# Display.net
KiCad netlist of a schematic drawn in Altium Designer
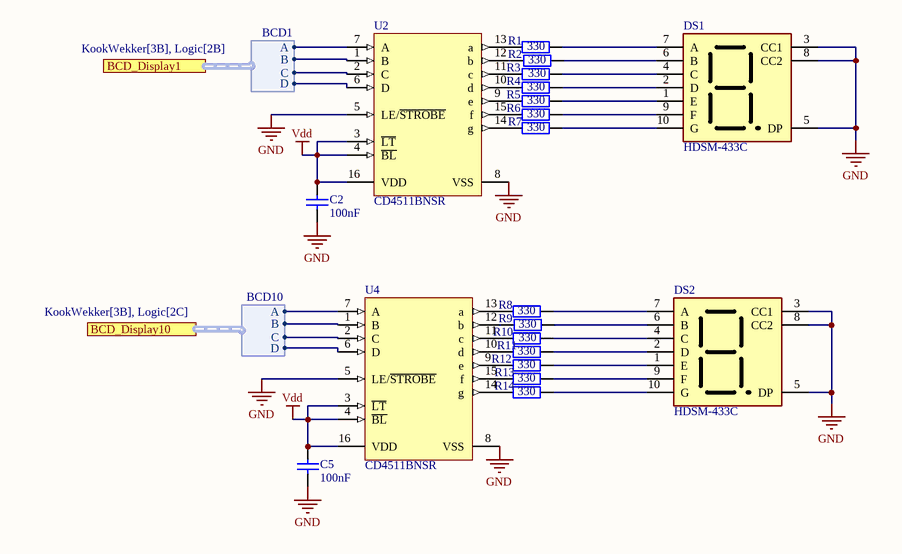
[diagram p0: Display.SchDoc]

(export (version "E")
  (design (tool "Eeschema 10.0.6"))
  (components
    (comp (ref "C2")
      (value "100nF")
      (footprint "C1206")
      (description "SMD Capacitor 1206")
      (fields (field (name "PUBLISHER") "Windesheim"))
      (libsource (lib "KookwekkerLibrary_v5_1") (part "Capacitor_1206"))
    )
    (comp (ref "C5")
      (value "100nF")
      (footprint "C1206")
      (description "SMD Capacitor 1206")
      (fields (field (name "PUBLISHER") "Windesheim"))
      (libsource (lib "KookwekkerLibrary_v5_1") (part "Capacitor_1206"))
    )
    (comp (ref "DS1")
      (value "HDSM-433C")
      (footprint "HDSM433C")
      (description "Display")
      (fields (field (name "MOUSER PART NUMBER") "630-HDSM-433C") (field (name "RS PART NUMBER") "1783057"))
      (libsource (lib "KookwekkerLibrary_v5_1") (part "HDSM-433C"))
    )
    (comp (ref "DS2")
      (value "HDSM-433C")
      (footprint "HDSM433C")
      (description "Display")
      (fields (field (name "MOUSER PART NUMBER") "630-HDSM-433C") (field (name "RS PART NUMBER") "1783057"))
      (libsource (lib "KookwekkerLibrary_v5_1") (part "HDSM-433C"))
    )
    (comp (ref "R1")
      (value "330")
      (footprint "R1206")
      (description "SMD Resistor 1206")
      (fields (field (name "PUBLISHER") "Windesheim"))
      (libsource (lib "KookwekkerLibrary_v5_1") (part "Resistor_1206"))
    )
    (comp (ref "R2")
      (value "330")
      (footprint "R1206")
      (description "SMD Resistor 1206")
      (fields (field (name "PUBLISHER") "Windesheim"))
      (libsource (lib "KookwekkerLibrary_v5_1") (part "Resistor_1206"))
    )
    (comp (ref "R3")
      (value "330")
      (footprint "R1206")
      (description "SMD Resistor 1206")
      (fields (field (name "PUBLISHER") "Windesheim"))
      (libsource (lib "KookwekkerLibrary_v5_1") (part "Resistor_1206"))
    )
    (comp (ref "R4")
      (value "330")
      (footprint "R1206")
      (description "SMD Resistor 1206")
      (fields (field (name "PUBLISHER") "Windesheim"))
      (libsource (lib "KookwekkerLibrary_v5_1") (part "Resistor_1206"))
    )
    (comp (ref "R5")
      (value "330")
      (footprint "R1206")
      (description "SMD Resistor 1206")
      (fields (field (name "PUBLISHER") "Windesheim"))
      (libsource (lib "KookwekkerLibrary_v5_1") (part "Resistor_1206"))
    )
    (comp (ref "R6")
      (value "330")
      (footprint "R1206")
      (description "SMD Resistor 1206")
      (fields (field (name "PUBLISHER") "Windesheim"))
      (libsource (lib "KookwekkerLibrary_v5_1") (part "Resistor_1206"))
    )
    (comp (ref "R7")
      (value "330")
      (footprint "R1206")
      (description "SMD Resistor 1206")
      (fields (field (name "PUBLISHER") "Windesheim"))
      (libsource (lib "KookwekkerLibrary_v5_1") (part "Resistor_1206"))
    )
    (comp (ref "R8")
      (value "330")
      (footprint "R1206")
      (description "SMD Resistor 1206")
      (fields (field (name "PUBLISHER") "Windesheim"))
      (libsource (lib "KookwekkerLibrary_v5_1") (part "Resistor_1206"))
    )
    (comp (ref "R9")
      (value "330")
      (footprint "R1206")
      (description "SMD Resistor 1206")
      (fields (field (name "PUBLISHER") "Windesheim"))
      (libsource (lib "KookwekkerLibrary_v5_1") (part "Resistor_1206"))
    )
    (comp (ref "R10")
      (value "330")
      (footprint "R1206")
      (description "SMD Resistor 1206")
      (fields (field (name "PUBLISHER") "Windesheim"))
      (libsource (lib "KookwekkerLibrary_v5_1") (part "Resistor_1206"))
    )
    (comp (ref "R11")
      (value "330")
      (footprint "R1206")
      (description "SMD Resistor 1206")
      (fields (field (name "PUBLISHER") "Windesheim"))
      (libsource (lib "KookwekkerLibrary_v5_1") (part "Resistor_1206"))
    )
    (comp (ref "R12")
      (value "330")
      (footprint "R1206")
      (description "SMD Resistor 1206")
      (fields (field (name "PUBLISHER") "Windesheim"))
      (libsource (lib "KookwekkerLibrary_v5_1") (part "Resistor_1206"))
    )
    (comp (ref "R13")
      (value "330")
      (footprint "R1206")
      (description "SMD Resistor 1206")
      (fields (field (name "PUBLISHER") "Windesheim"))
      (libsource (lib "KookwekkerLibrary_v5_1") (part "Resistor_1206"))
    )
    (comp (ref "R14")
      (value "330")
      (footprint "R1206")
      (description "SMD Resistor 1206")
      (fields (field (name "PUBLISHER") "Windesheim"))
      (libsource (lib "KookwekkerLibrary_v5_1") (part "Resistor_1206"))
    )
    (comp (ref "U2")
      (value "CD4511BNSR")
      (footprint "TI-NS16_N")
      (fields (field (name "MANUFACTURER") "Texas Instruments"))
      (libsource (lib "KookwekkerLibrary_v5_1") (part "CD4511BNSR"))
    )
    (comp (ref "U4")
      (value "CD4511BNSR")
      (footprint "TI-NS16_N")
      (fields (field (name "MANUFACTURER") "Texas Instruments"))
      (libsource (lib "KookwekkerLibrary_v5_1") (part "CD4511BNSR"))
    )
  )
  (nets
    (net (code "5") (name "GND") (class "Default")
      (node (ref "C2") (pin "1") (pinfunction "1_1") (pintype "passive"))
      (node (ref "C5") (pin "1") (pinfunction "1_1") (pintype "passive"))
      (node (ref "DS1") (pin "3") (pinfunction "CC1_3") (pintype "passive"))
      (node (ref "DS1") (pin "5") (pinfunction "DP_5") (pintype "passive"))
      (node (ref "DS1") (pin "8") (pinfunction "CC2_8") (pintype "passive"))
      (node (ref "DS2") (pin "3") (pinfunction "CC1_3") (pintype "passive"))
      (node (ref "DS2") (pin "5") (pinfunction "DP_5") (pintype "passive"))
      (node (ref "DS2") (pin "8") (pinfunction "CC2_8") (pintype "passive"))
      (node (ref "U2") (pin "5") (pinfunction "LE/~{STROBE}_5") (pintype "input"))
      (node (ref "U2") (pin "8") (pinfunction "VSS_8") (pintype "power_in"))
      (node (ref "U4") (pin "5") (pinfunction "LE/~{STROBE}_5") (pintype "input"))
      (node (ref "U4") (pin "8") (pinfunction "VSS_8") (pintype "power_in"))
    )
    (net (code "6") (name "Net-(DS1-A)") (class "Default")
      (node (ref "DS1") (pin "7") (pinfunction "A_7") (pintype "passive"))
      (node (ref "R1") (pin "2") (pinfunction "2_2") (pintype "passive"))
    )
    (net (code "7") (name "Net-(DS1-B)") (class "Default")
      (node (ref "DS1") (pin "6") (pinfunction "B_6") (pintype "passive"))
      (node (ref "R2") (pin "2") (pinfunction "2_2") (pintype "passive"))
    )
    (net (code "8") (name "Net-(DS1-C)") (class "Default")
      (node (ref "DS1") (pin "4") (pinfunction "C_4") (pintype "passive"))
      (node (ref "R3") (pin "2") (pinfunction "2_2") (pintype "passive"))
    )
    (net (code "9") (name "Net-(DS1-D)") (class "Default")
      (node (ref "DS1") (pin "2") (pinfunction "D_2") (pintype "passive"))
      (node (ref "R4") (pin "2") (pinfunction "2_2") (pintype "passive"))
    )
    (net (code "10") (name "Net-(DS1-E)") (class "Default")
      (node (ref "DS1") (pin "1") (pinfunction "E_1") (pintype "passive"))
      (node (ref "R5") (pin "2") (pinfunction "2_2") (pintype "passive"))
    )
    (net (code "11") (name "Net-(DS1-F)") (class "Default")
      (node (ref "DS1") (pin "9") (pinfunction "F_9") (pintype "passive"))
      (node (ref "R6") (pin "2") (pinfunction "2_2") (pintype "passive"))
    )
    (net (code "12") (name "Net-(DS1-G)") (class "Default")
      (node (ref "DS1") (pin "10") (pinfunction "G_10") (pintype "passive"))
      (node (ref "R7") (pin "2") (pinfunction "2_2") (pintype "passive"))
    )
    (net (code "13") (name "Net-(DS2-A)") (class "Default")
      (node (ref "DS2") (pin "7") (pinfunction "A_7") (pintype "passive"))
      (node (ref "R8") (pin "2") (pinfunction "2_2") (pintype "passive"))
    )
    (net (code "14") (name "Net-(DS2-B)") (class "Default")
      (node (ref "DS2") (pin "6") (pinfunction "B_6") (pintype "passive"))
      (node (ref "R9") (pin "2") (pinfunction "2_2") (pintype "passive"))
    )
    (net (code "15") (name "Net-(DS2-C)") (class "Default")
      (node (ref "DS2") (pin "4") (pinfunction "C_4") (pintype "passive"))
      (node (ref "R10") (pin "2") (pinfunction "2_2") (pintype "passive"))
    )
    (net (code "16") (name "Net-(DS2-D)") (class "Default")
      (node (ref "DS2") (pin "2") (pinfunction "D_2") (pintype "passive"))
      (node (ref "R11") (pin "2") (pinfunction "2_2") (pintype "passive"))
    )
    (net (code "17") (name "Net-(DS2-E)") (class "Default")
      (node (ref "DS2") (pin "1") (pinfunction "E_1") (pintype "passive"))
      (node (ref "R12") (pin "2") (pinfunction "2_2") (pintype "passive"))
    )
    (net (code "18") (name "Net-(DS2-F)") (class "Default")
      (node (ref "DS2") (pin "9") (pinfunction "F_9") (pintype "passive"))
      (node (ref "R13") (pin "2") (pinfunction "2_2") (pintype "passive"))
    )
    (net (code "19") (name "Net-(DS2-G)") (class "Default")
      (node (ref "DS2") (pin "10") (pinfunction "G_10") (pintype "passive"))
      (node (ref "R14") (pin "2") (pinfunction "2_2") (pintype "passive"))
    )
    (net (code "20") (name "Net-(U2-a)") (class "Default")
      (node (ref "R1") (pin "1") (pinfunction "1_1") (pintype "passive"))
      (node (ref "U2") (pin "13") (pinfunction "a_13") (pintype "output"))
    )
    (net (code "21") (name "Net-(U2-b)") (class "Default")
      (node (ref "R2") (pin "1") (pinfunction "1_1") (pintype "passive"))
      (node (ref "U2") (pin "12") (pinfunction "b_12") (pintype "output"))
    )
    (net (code "22") (name "Net-(U2-c)") (class "Default")
      (node (ref "R3") (pin "1") (pinfunction "1_1") (pintype "passive"))
      (node (ref "U2") (pin "11") (pinfunction "c_11") (pintype "output"))
    )
    (net (code "23") (name "Net-(U2-d)") (class "Default")
      (node (ref "R4") (pin "1") (pinfunction "1_1") (pintype "passive"))
      (node (ref "U2") (pin "10") (pinfunction "d_10") (pintype "output"))
    )
    (net (code "24") (name "Net-(U2-e)") (class "Default")
      (node (ref "R5") (pin "1") (pinfunction "1_1") (pintype "passive"))
      (node (ref "U2") (pin "9") (pinfunction "e_9") (pintype "output"))
    )
    (net (code "25") (name "Net-(U2-f)") (class "Default")
      (node (ref "R6") (pin "1") (pinfunction "1_1") (pintype "passive"))
      (node (ref "U2") (pin "15") (pinfunction "f_15") (pintype "output"))
    )
    (net (code "26") (name "Net-(U2-g)") (class "Default")
      (node (ref "R7") (pin "1") (pinfunction "1_1") (pintype "passive"))
      (node (ref "U2") (pin "14") (pinfunction "g_14") (pintype "output"))
    )
    (net (code "27") (name "Net-(U4-a)") (class "Default")
      (node (ref "R8") (pin "1") (pinfunction "1_1") (pintype "passive"))
      (node (ref "U4") (pin "13") (pinfunction "a_13") (pintype "output"))
    )
    (net (code "28") (name "Net-(U4-b)") (class "Default")
      (node (ref "R9") (pin "1") (pinfunction "1_1") (pintype "passive"))
      (node (ref "U4") (pin "12") (pinfunction "b_12") (pintype "output"))
    )
    (net (code "29") (name "Net-(U4-c)") (class "Default")
      (node (ref "R10") (pin "1") (pinfunction "1_1") (pintype "passive"))
      (node (ref "U4") (pin "11") (pinfunction "c_11") (pintype "output"))
    )
    (net (code "30") (name "Net-(U4-d)") (class "Default")
      (node (ref "R11") (pin "1") (pinfunction "1_1") (pintype "passive"))
      (node (ref "U4") (pin "10") (pinfunction "d_10") (pintype "output"))
    )
    (net (code "31") (name "Net-(U4-e)") (class "Default")
      (node (ref "R12") (pin "1") (pinfunction "1_1") (pintype "passive"))
      (node (ref "U4") (pin "9") (pinfunction "e_9") (pintype "output"))
    )
    (net (code "32") (name "Net-(U4-f)") (class "Default")
      (node (ref "R13") (pin "1") (pinfunction "1_1") (pintype "passive"))
      (node (ref "U4") (pin "15") (pinfunction "f_15") (pintype "output"))
    )
    (net (code "33") (name "Net-(U4-g)") (class "Default")
      (node (ref "R14") (pin "1") (pinfunction "1_1") (pintype "passive"))
      (node (ref "U4") (pin "14") (pinfunction "g_14") (pintype "output"))
    )
    (net (code "34") (name "Vdd") (class "Default")
      (node (ref "C2") (pin "2") (pinfunction "2_2") (pintype "passive"))
      (node (ref "C5") (pin "2") (pinfunction "2_2") (pintype "passive"))
      (node (ref "U2") (pin "16") (pinfunction "VDD_16") (pintype "power_in"))
      (node (ref "U2") (pin "3") (pinfunction "~{LT}_3") (pintype "input"))
      (node (ref "U2") (pin "4") (pinfunction "~{BL}_4") (pintype "input"))
      (node (ref "U4") (pin "16") (pinfunction "VDD_16") (pintype "power_in"))
      (node (ref "U4") (pin "3") (pinfunction "~{LT}_3") (pintype "input"))
      (node (ref "U4") (pin "4") (pinfunction "~{BL}_4") (pintype "input"))
    )
    (net (code "35") (name "unconnected-(U2-A-Pad7)") (class "Default")
      (node (ref "U2") (pin "7") (pinfunction "A_7") (pintype "input"))
    )
    (net (code "36") (name "unconnected-(U2-B-Pad1)") (class "Default")
      (node (ref "U2") (pin "1") (pinfunction "B_1") (pintype "input"))
    )
    (net (code "37") (name "unconnected-(U2-C-Pad2)") (class "Default")
      (node (ref "U2") (pin "2") (pinfunction "C_2") (pintype "input"))
    )
    (net (code "38") (name "unconnected-(U2-D-Pad6)") (class "Default")
      (node (ref "U2") (pin "6") (pinfunction "D_6") (pintype "input"))
    )
    (net (code "39") (name "unconnected-(U4-A-Pad7)") (class "Default")
      (node (ref "U4") (pin "7") (pinfunction "A_7") (pintype "input"))
    )
    (net (code "40") (name "unconnected-(U4-B-Pad1)") (class "Default")
      (node (ref "U4") (pin "1") (pinfunction "B_1") (pintype "input"))
    )
    (net (code "41") (name "unconnected-(U4-C-Pad2)") (class "Default")
      (node (ref "U4") (pin "2") (pinfunction "C_2") (pintype "input"))
    )
    (net (code "42") (name "unconnected-(U4-D-Pad6)") (class "Default")
      (node (ref "U4") (pin "6") (pinfunction "D_6") (pintype "input"))
    )
  )
)
